# EspPinExtender.net
KiCad netlist of a schematic drawn in EAGLE
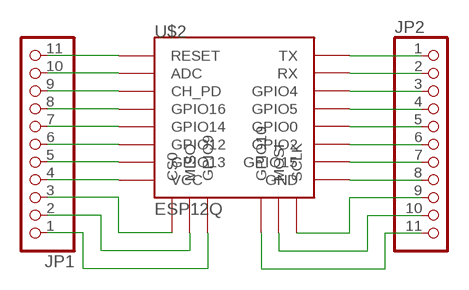
[diagram p0: schematic, sheet 1]

(export (version "E")
  (design (tool "Eeschema 10.0.6"))
  (components
    (comp (ref "JP1")
      (value "PINHD-1X11")
      (footprint "eagle-import:1X11")
      (libsource (lib "eagle-import") (part "PINHD-1X11"))
    )
    (comp (ref "JP2")
      (value "PINHD-1X11")
      (footprint "eagle-import:1X11")
      (libsource (lib "eagle-import") (part "PINHD-1X11"))
    )
    (comp (ref "U$2")
      (value "ESP12Q")
      (footprint "eagle-import:ESP12Q")
      (libsource (lib "eagle-import") (part "ESP12Q"))
    )
  )
  (nets
    (net (code "1") (name "Net-(JP1-Pad1)") (class "Default")
      (node (ref "JP1") (pin "1") (pinfunction "1_1") (pintype "passive"))
      (node (ref "U$2") (pin "GPIO9") (pinfunction "GPIO9_GPIO9") (pintype "bidirectional"))
    )
    (net (code "2") (name "Net-(JP1-Pad2)") (class "Default")
      (node (ref "JP1") (pin "2") (pinfunction "2_2") (pintype "passive"))
      (node (ref "U$2") (pin "MISO") (pinfunction "MISO_MISO") (pintype "bidirectional"))
    )
    (net (code "3") (name "Net-(JP1-Pad3)") (class "Default")
      (node (ref "JP1") (pin "3") (pinfunction "3_3") (pintype "passive"))
      (node (ref "U$2") (pin "CS0") (pinfunction "CS0_CS0") (pintype "bidirectional"))
    )
    (net (code "4") (name "Net-(JP1-Pad4)") (class "Default")
      (node (ref "JP1") (pin "4") (pinfunction "4_4") (pintype "passive"))
      (node (ref "U$2") (pin "VCC") (pinfunction "VCC_VCC") (pintype "bidirectional"))
    )
    (net (code "5") (name "Net-(JP1-Pad5)") (class "Default")
      (node (ref "JP1") (pin "5") (pinfunction "5_5") (pintype "passive"))
      (node (ref "U$2") (pin "GPIO13") (pinfunction "GPIO13_GPIO13") (pintype "bidirectional"))
    )
    (net (code "6") (name "Net-(JP1-Pad6)") (class "Default")
      (node (ref "JP1") (pin "6") (pinfunction "6_6") (pintype "passive"))
      (node (ref "U$2") (pin "GPIO12") (pinfunction "GPIO12_GPIO12") (pintype "bidirectional"))
    )
    (net (code "7") (name "Net-(JP1-Pad7)") (class "Default")
      (node (ref "JP1") (pin "7") (pinfunction "7_7") (pintype "passive"))
      (node (ref "U$2") (pin "GPIO14") (pinfunction "GPIO14_GPIO14") (pintype "bidirectional"))
    )
    (net (code "8") (name "Net-(JP1-Pad8)") (class "Default")
      (node (ref "JP1") (pin "8") (pinfunction "8_8") (pintype "passive"))
      (node (ref "U$2") (pin "GPIO16") (pinfunction "GPIO16_GPIO16") (pintype "bidirectional"))
    )
    (net (code "9") (name "Net-(JP1-Pad9)") (class "Default")
      (node (ref "JP1") (pin "9") (pinfunction "9_9") (pintype "passive"))
      (node (ref "U$2") (pin "CH_PD") (pinfunction "CH_PD_CH_PD") (pintype "bidirectional"))
    )
    (net (code "10") (name "Net-(JP1-Pad10)") (class "Default")
      (node (ref "JP1") (pin "10") (pinfunction "10_10") (pintype "passive"))
      (node (ref "U$2") (pin "ADC") (pinfunction "ADC_ADC") (pintype "bidirectional"))
    )
    (net (code "11") (name "Net-(JP1-Pad11)") (class "Default")
      (node (ref "JP1") (pin "11") (pinfunction "11_11") (pintype "passive"))
      (node (ref "U$2") (pin "RESET") (pinfunction "RESET_RESET") (pintype "bidirectional"))
    )
    (net (code "12") (name "Net-(JP2-Pad1)") (class "Default")
      (node (ref "JP2") (pin "1") (pinfunction "1_1") (pintype "passive"))
      (node (ref "U$2") (pin "TX") (pinfunction "TX_TX") (pintype "bidirectional"))
    )
    (net (code "13") (name "Net-(JP2-Pad2)") (class "Default")
      (node (ref "JP2") (pin "2") (pinfunction "2_2") (pintype "passive"))
      (node (ref "U$2") (pin "RX") (pinfunction "RX_RX") (pintype "bidirectional"))
    )
    (net (code "14") (name "Net-(JP2-Pad3)") (class "Default")
      (node (ref "JP2") (pin "3") (pinfunction "3_3") (pintype "passive"))
      (node (ref "U$2") (pin "GPIO4") (pinfunction "GPIO4_GPIO4") (pintype "bidirectional"))
    )
    (net (code "15") (name "Net-(JP2-Pad4)") (class "Default")
      (node (ref "JP2") (pin "4") (pinfunction "4_4") (pintype "passive"))
      (node (ref "U$2") (pin "GPIO5") (pinfunction "GPIO5_GPIO5") (pintype "bidirectional"))
    )
    (net (code "16") (name "Net-(JP2-Pad5)") (class "Default")
      (node (ref "JP2") (pin "5") (pinfunction "5_5") (pintype "passive"))
      (node (ref "U$2") (pin "GPIO0") (pinfunction "GPIO0_GPIO0") (pintype "bidirectional"))
    )
    (net (code "17") (name "Net-(JP2-Pad6)") (class "Default")
      (node (ref "JP2") (pin "6") (pinfunction "6_6") (pintype "passive"))
      (node (ref "U$2") (pin "GPIO2") (pinfunction "GPIO2_GPIO2") (pintype "bidirectional"))
    )
    (net (code "18") (name "Net-(JP2-Pad7)") (class "Default")
      (node (ref "JP2") (pin "7") (pinfunction "7_7") (pintype "passive"))
      (node (ref "U$2") (pin "GPIO15") (pinfunction "GPIO15_GPIO15") (pintype "bidirectional"))
    )
    (net (code "19") (name "Net-(JP2-Pad8)") (class "Default")
      (node (ref "JP2") (pin "8") (pinfunction "8_8") (pintype "passive"))
      (node (ref "U$2") (pin "GND") (pinfunction "GND_GND") (pintype "bidirectional"))
    )
    (net (code "20") (name "Net-(JP2-Pad9)") (class "Default")
      (node (ref "JP2") (pin "9") (pinfunction "9_9") (pintype "passive"))
      (node (ref "U$2") (pin "SCLK") (pinfunction "SCLK_SCLK") (pintype "bidirectional"))
    )
    (net (code "21") (name "Net-(JP2-Pad10)") (class "Default")
      (node (ref "JP2") (pin "10") (pinfunction "10_10") (pintype "passive"))
      (node (ref "U$2") (pin "MOSI") (pinfunction "MOSI_MOSI") (pintype "bidirectional"))
    )
    (net (code "22") (name "Net-(JP2-Pad11)") (class "Default")
      (node (ref "JP2") (pin "11") (pinfunction "11_11") (pintype "passive"))
      (node (ref "U$2") (pin "GPIO10") (pinfunction "GPIO10_GPIO10") (pintype "bidirectional"))
    )
  )
)
